# swdtousb.net
KiCad netlist of a schematic drawn in EAGLE
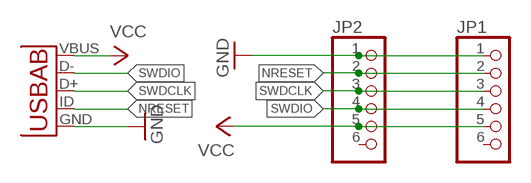
[diagram p0: schematic, sheet 1]

(export (version "E")
  (design (tool "Eeschema 10.0.6"))
  (components
    (comp (ref "JP1")
      (value "PINHD-1X6")
      (footprint "eagle-import:1X06")
      (libsource (lib "eagle-import") (part "PINHD-1X6"))
    )
    (comp (ref "JP2")
      (value "PINHD-1X6")
      (footprint "eagle-import:1X06")
      (libsource (lib "eagle-import") (part "PINHD-1X6"))
    )
    (comp (ref "U1")
      (value "USB-AB")
      (footprint "eagle-import:USB-AB-MICRO")
      (libsource (lib "eagle-import") (part "USB-AB"))
    )
  )
  (nets
    (net (code "1") (name "GND") (class "Default")
      (node (ref "JP1") (pin "1") (pinfunction "1_1") (pintype "passive"))
      (node (ref "JP2") (pin "1") (pinfunction "1_1") (pintype "passive"))
      (node (ref "U1") (pin "GND") (pinfunction "GND_GND") (pintype "bidirectional"))
    )
    (net (code "2") (name "NRESET") (class "Default")
      (node (ref "JP1") (pin "2") (pinfunction "2_2") (pintype "passive"))
      (node (ref "JP2") (pin "2") (pinfunction "2_2") (pintype "passive"))
      (node (ref "U1") (pin "ID") (pinfunction "USBID_ID") (pintype "bidirectional"))
    )
    (net (code "3") (name "SWDCLK") (class "Default")
      (node (ref "JP1") (pin "3") (pinfunction "3_3") (pintype "passive"))
      (node (ref "JP2") (pin "3") (pinfunction "3_3") (pintype "passive"))
      (node (ref "U1") (pin "D+") (pinfunction "D+_D+") (pintype "bidirectional"))
    )
    (net (code "4") (name "SWDIO") (class "Default")
      (node (ref "JP1") (pin "4") (pinfunction "4_4") (pintype "passive"))
      (node (ref "JP2") (pin "4") (pinfunction "4_4") (pintype "passive"))
      (node (ref "U1") (pin "D-") (pinfunction "D-_D-") (pintype "bidirectional"))
    )
    (net (code "5") (name "VCC") (class "Default")
      (node (ref "JP1") (pin "5") (pinfunction "5_5") (pintype "passive"))
      (node (ref "JP2") (pin "5") (pinfunction "5_5") (pintype "passive"))
      (node (ref "U1") (pin "VBUS") (pinfunction "VBUS_VBUS") (pintype "bidirectional"))
    )
    (net (code "6") (name "unconnected-(JP1-Pad6)") (class "Default")
      (node (ref "JP1") (pin "6") (pinfunction "6_6") (pintype "passive"))
    )
    (net (code "7") (name "unconnected-(JP2-Pad6)") (class "Default")
      (node (ref "JP2") (pin "6") (pinfunction "6_6") (pintype "passive"))
    )
  )
)
